# Push-It-V1_1.net
KiCad netlist of a schematic drawn in EAGLE
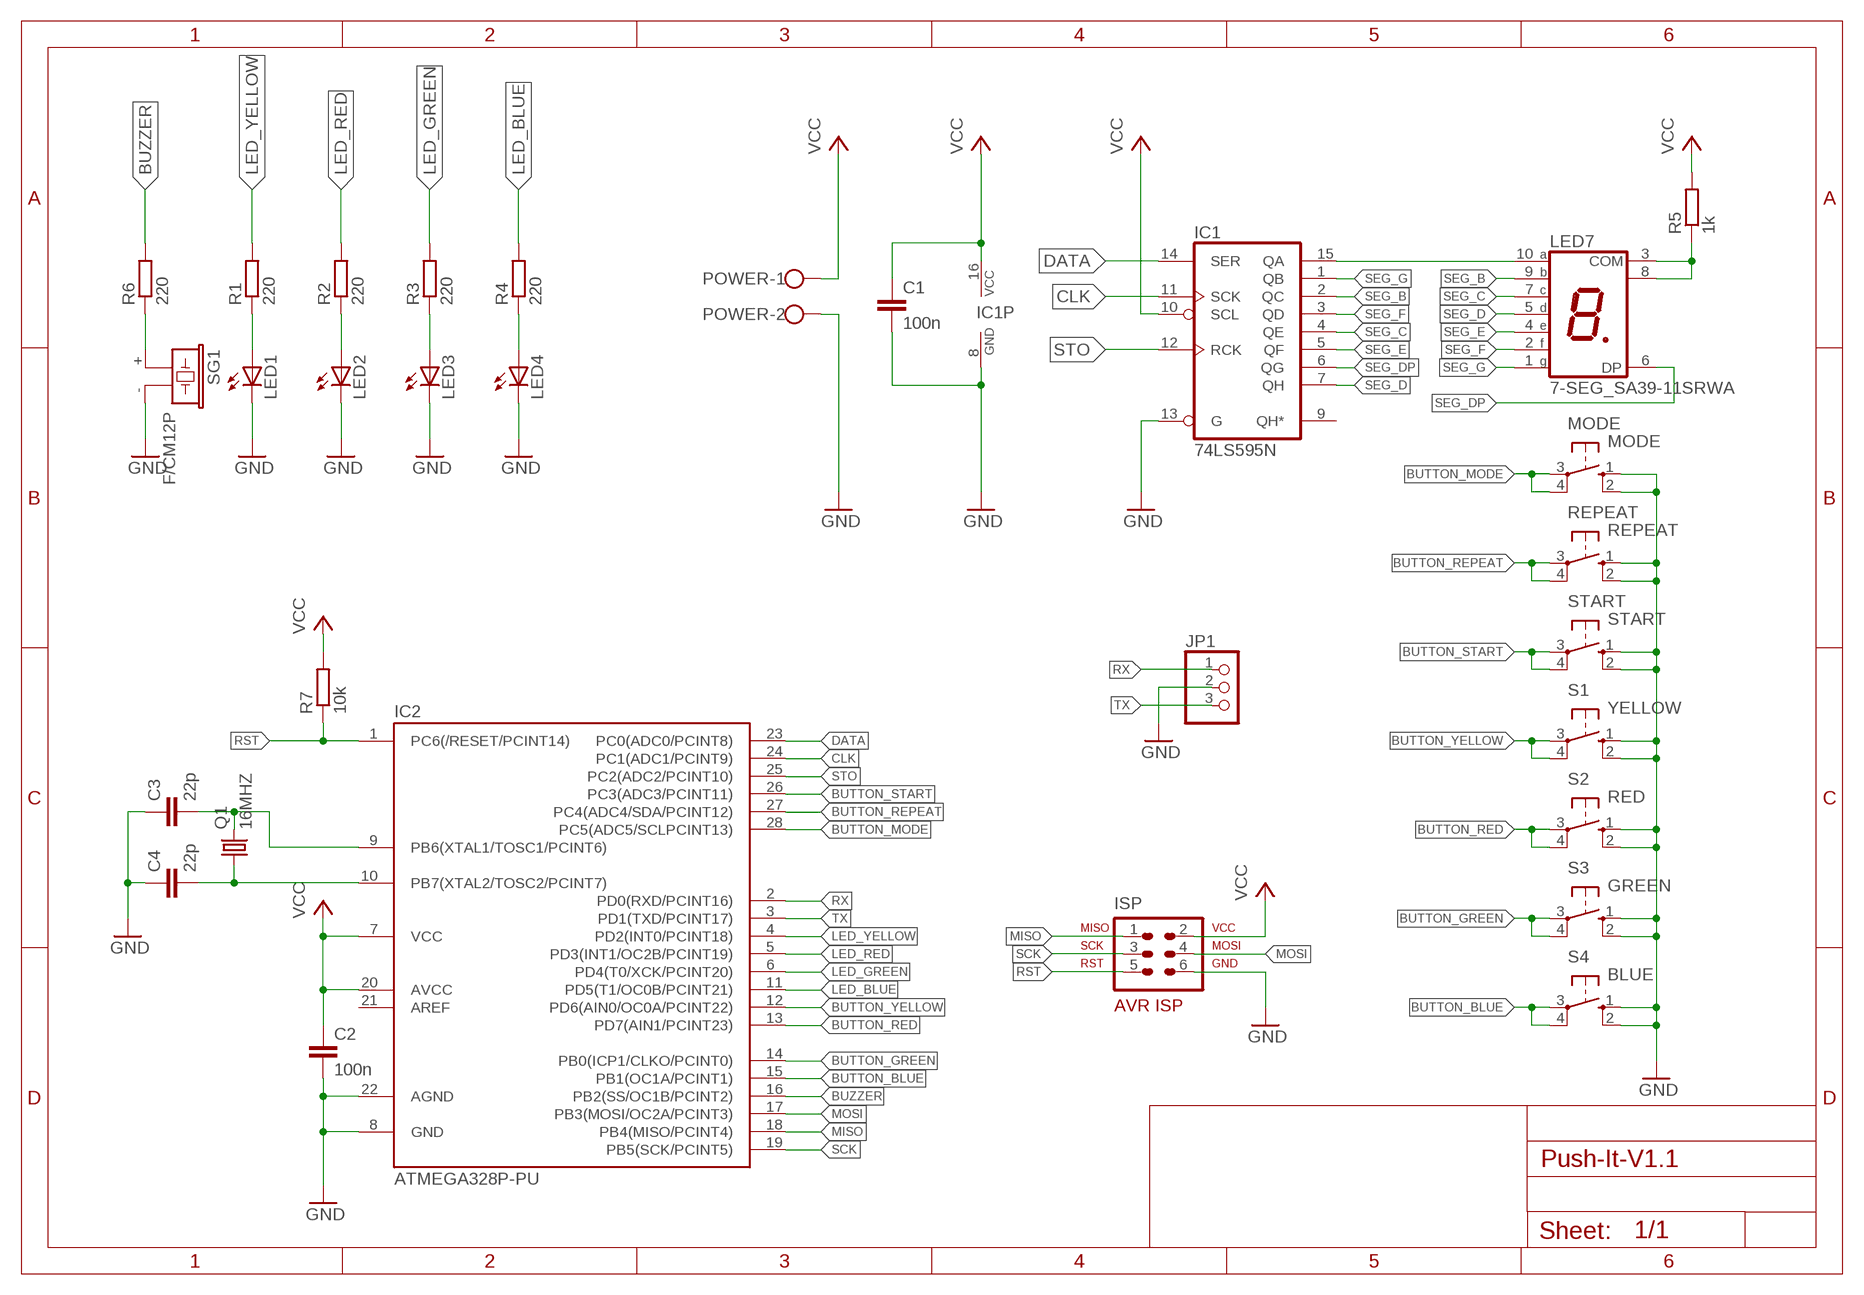
[diagram p0: schematic, sheet 1]

(export (version "E")
  (design (tool "Eeschema 10.0.6"))
  (components
    (comp (ref "C1")
      (value "100n")
      (footprint "eagle-import:C025-025X050")
      (libsource (lib "eagle-import") (part "C-EU025-025X050"))
    )
    (comp (ref "C2")
      (value "100n")
      (footprint "eagle-import:C025-025X050")
      (libsource (lib "eagle-import") (part "C-EU025-025X050"))
    )
    (comp (ref "C3")
      (value "22p")
      (footprint "eagle-import:C025-025X050")
      (libsource (lib "eagle-import") (part "C-EU025-025X050"))
    )
    (comp (ref "C4")
      (value "22p")
      (footprint "eagle-import:C025-025X050")
      (libsource (lib "eagle-import") (part "C-EU025-025X050"))
    )
    (comp (ref "IC1")
      (value "74LS595N")
      (footprint "eagle-import:DIL16")
      (libsource (lib "eagle-import") (part "74595NLS"))
    )
    (comp (ref "IC2")
      (value "ATMEGA328P-PU")
      (footprint "eagle-import:DIL28-3")
      (libsource (lib "eagle-import") (part "MEGA48/88/168-PU"))
    )
    (comp (ref "ISP")
      (value "AVR-ISP-6VERT")
      (footprint "eagle-import:AVR-ISP-6")
      (libsource (lib "eagle-import") (part "AVR-ISP-6VERT"))
    )
    (comp (ref "JP1")
      (value "PINHD-1X3/90")
      (footprint "eagle-import:1X03_90")
      (libsource (lib "eagle-import") (part "PINHD-1X3/90"))
    )
    (comp (ref "LED1")
      (value "LED10MM")
      (footprint "eagle-import:LED10MM")
      (libsource (lib "eagle-import") (part "LED10MM"))
    )
    (comp (ref "LED2")
      (value "LED10MM")
      (footprint "eagle-import:LED10MM")
      (libsource (lib "eagle-import") (part "LED10MM"))
    )
    (comp (ref "LED3")
      (value "LED10MM")
      (footprint "eagle-import:LED10MM")
      (libsource (lib "eagle-import") (part "LED10MM"))
    )
    (comp (ref "LED4")
      (value "LED10MM")
      (footprint "eagle-import:LED10MM")
      (libsource (lib "eagle-import") (part "LED10MM"))
    )
    (comp (ref "LED7")
      (value "7-SEG_SA39-11SRWA")
      (footprint "eagle-import:SA39-11SRWA")
      (libsource (lib "eagle-import") (part "7-SEG_SA39-11SRWA"))
    )
    (comp (ref "MODE")
      (value "MODE")
      (footprint "eagle-import:B3F-10XX")
      (fields (field (name "MPN") "B3F-1000"))
      (libsource (lib "eagle-import") (part "10-XX"))
    )
    (comp (ref "POWER")
      (value "W237-102")
      (footprint "eagle-import:W237-102")
      (fields (field (name "MPN") "237-102"))
      (libsource (lib "eagle-import") (part "W237-102"))
    )
    (comp (ref "Q1")
      (value "16MHZ")
      (footprint "eagle-import:HC49_S")
      (libsource (lib "eagle-import") (part "CRYSTALHC49S"))
    )
    (comp (ref "R1")
      (value "220")
      (footprint "eagle-import:0207_7")
      (libsource (lib "eagle-import") (part "R-EU_0207/7"))
    )
    (comp (ref "R2")
      (value "220")
      (footprint "eagle-import:0207_7")
      (libsource (lib "eagle-import") (part "R-EU_0207/7"))
    )
    (comp (ref "R3")
      (value "220")
      (footprint "eagle-import:0207_7")
      (libsource (lib "eagle-import") (part "R-EU_0207/7"))
    )
    (comp (ref "R4")
      (value "220")
      (footprint "eagle-import:0207_7")
      (libsource (lib "eagle-import") (part "R-EU_0207/7"))
    )
    (comp (ref "R5")
      (value "1k")
      (footprint "eagle-import:0207_7")
      (libsource (lib "eagle-import") (part "R-EU_0207/7"))
    )
    (comp (ref "R6")
      (value "220")
      (footprint "eagle-import:0207_7")
      (libsource (lib "eagle-import") (part "R-EU_0207/7"))
    )
    (comp (ref "R7")
      (value "10k")
      (footprint "eagle-import:0207_7")
      (libsource (lib "eagle-import") (part "R-EU_0207/7"))
    )
    (comp (ref "REPEAT")
      (value "REPEAT")
      (footprint "eagle-import:B3F-10XX")
      (fields (field (name "MPN") "B3F-1000"))
      (libsource (lib "eagle-import") (part "10-XX"))
    )
    (comp (ref "S1")
      (value "YELLOW")
      (footprint "eagle-import:B3F-10XX")
      (fields (field (name "MPN") "B3F-1000"))
      (libsource (lib "eagle-import") (part "10-XX"))
    )
    (comp (ref "S2")
      (value "RED")
      (footprint "eagle-import:B3F-10XX")
      (fields (field (name "MPN") "B3F-1000"))
      (libsource (lib "eagle-import") (part "10-XX"))
    )
    (comp (ref "S3")
      (value "GREEN")
      (footprint "eagle-import:B3F-10XX")
      (fields (field (name "MPN") "B3F-1000"))
      (libsource (lib "eagle-import") (part "10-XX"))
    )
    (comp (ref "S4")
      (value "BLUE")
      (footprint "eagle-import:B3F-10XX")
      (fields (field (name "MPN") "B3F-1000"))
      (libsource (lib "eagle-import") (part "10-XX"))
    )
    (comp (ref "SG1")
      (value "F/CM12P")
      (footprint "eagle-import:F_CM12P")
      (libsource (lib "eagle-import") (part "F/CM12P"))
    )
    (comp (ref "START")
      (value "START")
      (footprint "eagle-import:B3F-10XX")
      (fields (field (name "MPN") "B3F-1000"))
      (libsource (lib "eagle-import") (part "10-XX"))
    )
  )
  (nets
    (net (code "1") (name "BUTTON_BLUE") (class "Default")
      (node (ref "IC2") (pin "15") (pinfunction "PB1(OC1A/PCINT1)_15") (pintype "bidirectional"))
      (node (ref "S4") (pin "3") (pinfunction "P_3") (pintype "passive"))
      (node (ref "S4") (pin "4") (pinfunction "P1_4") (pintype "passive"))
    )
    (net (code "2") (name "BUTTON_GREEN") (class "Default")
      (node (ref "IC2") (pin "14") (pinfunction "PB0(ICP1/CLKO/PCINT0)_14") (pintype "bidirectional"))
      (node (ref "S3") (pin "3") (pinfunction "P_3") (pintype "passive"))
      (node (ref "S3") (pin "4") (pinfunction "P1_4") (pintype "passive"))
    )
    (net (code "3") (name "BUTTON_MODE") (class "Default")
      (node (ref "IC2") (pin "28") (pinfunction "PC5(ADC5/SCLPCINT13)_28") (pintype "bidirectional"))
      (node (ref "MODE") (pin "3") (pinfunction "P_3") (pintype "passive"))
      (node (ref "MODE") (pin "4") (pinfunction "P1_4") (pintype "passive"))
    )
    (net (code "4") (name "BUTTON_RED") (class "Default")
      (node (ref "IC2") (pin "13") (pinfunction "PD7(AIN1/PCINT23)_13") (pintype "bidirectional"))
      (node (ref "S2") (pin "3") (pinfunction "P_3") (pintype "passive"))
      (node (ref "S2") (pin "4") (pinfunction "P1_4") (pintype "passive"))
    )
    (net (code "5") (name "BUTTON_REPEAT") (class "Default")
      (node (ref "IC2") (pin "27") (pinfunction "PC4(ADC4/SDA/PCINT12)_27") (pintype "bidirectional"))
      (node (ref "REPEAT") (pin "3") (pinfunction "P_3") (pintype "passive"))
      (node (ref "REPEAT") (pin "4") (pinfunction "P1_4") (pintype "passive"))
    )
    (net (code "6") (name "BUTTON_START") (class "Default")
      (node (ref "IC2") (pin "26") (pinfunction "PC3(ADC3/PCINT11)_26") (pintype "bidirectional"))
      (node (ref "START") (pin "3") (pinfunction "P_3") (pintype "passive"))
      (node (ref "START") (pin "4") (pinfunction "P1_4") (pintype "passive"))
    )
    (net (code "7") (name "BUTTON_YELLOW") (class "Default")
      (node (ref "IC2") (pin "12") (pinfunction "PD6(AIN0/OC0A/PCINT22)_12") (pintype "bidirectional"))
      (node (ref "S1") (pin "3") (pinfunction "P_3") (pintype "passive"))
      (node (ref "S1") (pin "4") (pinfunction "P1_4") (pintype "passive"))
    )
    (net (code "8") (name "BUZZER") (class "Default")
      (node (ref "IC2") (pin "16") (pinfunction "PB2(SS/OC1B/PCINT2)_16") (pintype "bidirectional"))
      (node (ref "R6") (pin "2") (pinfunction "2_2") (pintype "passive"))
    )
    (net (code "9") (name "CLK") (class "Default")
      (node (ref "IC1") (pin "11") (pinfunction "SCK_11") (pintype "input"))
      (node (ref "IC2") (pin "24") (pinfunction "PC1(ADC1/PCINT9)_24") (pintype "bidirectional"))
    )
    (net (code "10") (name "DATA") (class "Default")
      (node (ref "IC1") (pin "14") (pinfunction "SER_14") (pintype "input"))
      (node (ref "IC2") (pin "23") (pinfunction "PC0(ADC0/PCINT8)_23") (pintype "bidirectional"))
    )
    (net (code "11") (name "GND") (class "Default")
      (node (ref "C1") (pin "2") (pinfunction "2_2") (pintype "passive"))
      (node (ref "C2") (pin "2") (pinfunction "2_2") (pintype "passive"))
      (node (ref "C3") (pin "1") (pinfunction "1_1") (pintype "passive"))
      (node (ref "C4") (pin "1") (pinfunction "1_1") (pintype "passive"))
      (node (ref "IC1") (pin "13") (pinfunction "G_13") (pintype "input"))
      (node (ref "IC1") (pin "8") (pinfunction "GND_8") (pintype "power_in"))
      (node (ref "IC2") (pin "22") (pinfunction "AGND_22") (pintype "power_in"))
      (node (ref "IC2") (pin "8") (pinfunction "GND_8") (pintype "power_in"))
      (node (ref "ISP") (pin "6") (pinfunction "6_6") (pintype "passive"))
      (node (ref "JP1") (pin "2") (pinfunction "2_2") (pintype "passive"))
      (node (ref "LED1") (pin "K") (pinfunction "C_K") (pintype "passive"))
      (node (ref "LED2") (pin "K") (pinfunction "C_K") (pintype "passive"))
      (node (ref "LED3") (pin "K") (pinfunction "C_K") (pintype "passive"))
      (node (ref "LED4") (pin "K") (pinfunction "C_K") (pintype "passive"))
      (node (ref "MODE") (pin "1") (pinfunction "S_1") (pintype "passive"))
      (node (ref "MODE") (pin "2") (pinfunction "S1_2") (pintype "passive"))
      (node (ref "POWER") (pin "2") (pinfunction "KL_2") (pintype "passive"))
      (node (ref "REPEAT") (pin "1") (pinfunction "S_1") (pintype "passive"))
      (node (ref "REPEAT") (pin "2") (pinfunction "S1_2") (pintype "passive"))
      (node (ref "S1") (pin "1") (pinfunction "S_1") (pintype "passive"))
      (node (ref "S1") (pin "2") (pinfunction "S1_2") (pintype "passive"))
      (node (ref "S2") (pin "1") (pinfunction "S_1") (pintype "passive"))
      (node (ref "S2") (pin "2") (pinfunction "S1_2") (pintype "passive"))
      (node (ref "S3") (pin "1") (pinfunction "S_1") (pintype "passive"))
      (node (ref "S3") (pin "2") (pinfunction "S1_2") (pintype "passive"))
      (node (ref "S4") (pin "1") (pinfunction "S_1") (pintype "passive"))
      (node (ref "S4") (pin "2") (pinfunction "S1_2") (pintype "passive"))
      (node (ref "SG1") (pin "-") (pinfunction "2_-") (pintype "passive"))
      (node (ref "START") (pin "1") (pinfunction "S_1") (pintype "passive"))
      (node (ref "START") (pin "2") (pinfunction "S1_2") (pintype "passive"))
    )
    (net (code "12") (name "LED_BLUE") (class "Default")
      (node (ref "IC2") (pin "11") (pinfunction "PD5(T1/OC0B/PCINT21)_11") (pintype "bidirectional"))
      (node (ref "R4") (pin "2") (pinfunction "2_2") (pintype "passive"))
    )
    (net (code "13") (name "LED_GREEN") (class "Default")
      (node (ref "IC2") (pin "6") (pinfunction "PD4(T0/XCK/PCINT20)_6") (pintype "bidirectional"))
      (node (ref "R3") (pin "2") (pinfunction "2_2") (pintype "passive"))
    )
    (net (code "14") (name "LED_RED") (class "Default")
      (node (ref "IC2") (pin "5") (pinfunction "PD3(INT1/OC2B/PCINT19)_5") (pintype "bidirectional"))
      (node (ref "R2") (pin "2") (pinfunction "2_2") (pintype "passive"))
    )
    (net (code "15") (name "LED_YELLOW") (class "Default")
      (node (ref "IC2") (pin "4") (pinfunction "PD2(INT0/PCINT18)_4") (pintype "bidirectional"))
      (node (ref "R1") (pin "2") (pinfunction "2_2") (pintype "passive"))
    )
    (net (code "16") (name "MISO") (class "Default")
      (node (ref "IC2") (pin "18") (pinfunction "PB4(MISO/PCINT4)_18") (pintype "bidirectional"))
      (node (ref "ISP") (pin "1") (pinfunction "1_1") (pintype "passive"))
    )
    (net (code "17") (name "MOSI") (class "Default")
      (node (ref "IC2") (pin "17") (pinfunction "PB3(MOSI/OC2A/PCINT3)_17") (pintype "bidirectional"))
      (node (ref "ISP") (pin "4") (pinfunction "4_4") (pintype "passive"))
    )
    (net (code "18") (name "Net-(IC1A-QA)") (class "Default")
      (node (ref "IC1") (pin "15") (pinfunction "QA_15") (pintype "tri_state"))
      (node (ref "LED7") (pin "10") (pinfunction "A_10") (pintype "passive"))
    )
    (net (code "19") (name "Net-(IC2-PB6(XTAL1{slash}TOSC1{slash}PCINT6))") (class "Default")
      (node (ref "C3") (pin "2") (pinfunction "2_2") (pintype "passive"))
      (node (ref "IC2") (pin "9") (pinfunction "PB6(XTAL1/TOSC1/PCINT6)_9") (pintype "bidirectional"))
      (node (ref "Q1") (pin "2") (pinfunction "2_2") (pintype "passive"))
    )
    (net (code "20") (name "Net-(IC2-PB7(XTAL2{slash}TOSC2{slash}PCINT7))") (class "Default")
      (node (ref "C4") (pin "2") (pinfunction "2_2") (pintype "passive"))
      (node (ref "IC2") (pin "10") (pinfunction "PB7(XTAL2/TOSC2/PCINT7)_10") (pintype "bidirectional"))
      (node (ref "Q1") (pin "1") (pinfunction "1_1") (pintype "passive"))
    )
    (net (code "21") (name "Net-(LED1-PadA)") (class "Default")
      (node (ref "LED1") (pin "A") (pinfunction "A_A") (pintype "passive"))
      (node (ref "R1") (pin "1") (pinfunction "1_1") (pintype "passive"))
    )
    (net (code "22") (name "Net-(LED2-PadA)") (class "Default")
      (node (ref "LED2") (pin "A") (pinfunction "A_A") (pintype "passive"))
      (node (ref "R2") (pin "1") (pinfunction "1_1") (pintype "passive"))
    )
    (net (code "23") (name "Net-(LED3-PadA)") (class "Default")
      (node (ref "LED3") (pin "A") (pinfunction "A_A") (pintype "passive"))
      (node (ref "R3") (pin "1") (pinfunction "1_1") (pintype "passive"))
    )
    (net (code "24") (name "Net-(LED4-PadA)") (class "Default")
      (node (ref "LED4") (pin "A") (pinfunction "A_A") (pintype "passive"))
      (node (ref "R4") (pin "1") (pinfunction "1_1") (pintype "passive"))
    )
    (net (code "25") (name "Net-(LED7-COM-Pad3)") (class "Default")
      (node (ref "LED7") (pin "3") (pinfunction "COM_3") (pintype "passive"))
      (node (ref "LED7") (pin "8") (pinfunction "COM_8") (pintype "passive"))
      (node (ref "R5") (pin "1") (pinfunction "1_1") (pintype "passive"))
    )
    (net (code "26") (name "Net-(SG1-1)") (class "Default")
      (node (ref "R6") (pin "1") (pinfunction "1_1") (pintype "passive"))
      (node (ref "SG1") (pin "+") (pinfunction "1_+") (pintype "passive"))
    )
    (net (code "27") (name "RST") (class "Default")
      (node (ref "IC2") (pin "1") (pinfunction "PC6(/RESET/PCINT14)_1") (pintype "bidirectional"))
      (node (ref "ISP") (pin "5") (pinfunction "5_5") (pintype "passive"))
      (node (ref "R7") (pin "1") (pinfunction "1_1") (pintype "passive"))
    )
    (net (code "28") (name "RX") (class "Default")
      (node (ref "IC2") (pin "2") (pinfunction "PD0(RXD/PCINT16)_2") (pintype "bidirectional"))
      (node (ref "JP1") (pin "1") (pinfunction "1_1") (pintype "passive"))
    )
    (net (code "29") (name "SCK") (class "Default")
      (node (ref "IC2") (pin "19") (pinfunction "PB5(SCK/PCINT5)_19") (pintype "bidirectional"))
      (node (ref "ISP") (pin "3") (pinfunction "3_3") (pintype "passive"))
    )
    (net (code "30") (name "SEG_B") (class "Default")
      (node (ref "IC1") (pin "2") (pinfunction "QC_2") (pintype "tri_state"))
      (node (ref "LED7") (pin "9") (pinfunction "B_9") (pintype "passive"))
    )
    (net (code "31") (name "SEG_C") (class "Default")
      (node (ref "IC1") (pin "4") (pinfunction "QE_4") (pintype "tri_state"))
      (node (ref "LED7") (pin "7") (pinfunction "C_7") (pintype "passive"))
    )
    (net (code "32") (name "SEG_D") (class "Default")
      (node (ref "IC1") (pin "7") (pinfunction "QH_7") (pintype "tri_state"))
      (node (ref "LED7") (pin "5") (pinfunction "D_5") (pintype "passive"))
    )
    (net (code "33") (name "SEG_DP") (class "Default")
      (node (ref "IC1") (pin "6") (pinfunction "QG_6") (pintype "tri_state"))
      (node (ref "LED7") (pin "6") (pinfunction "DP_6") (pintype "passive"))
    )
    (net (code "34") (name "SEG_E") (class "Default")
      (node (ref "IC1") (pin "5") (pinfunction "QF_5") (pintype "tri_state"))
      (node (ref "LED7") (pin "4") (pinfunction "E_4") (pintype "passive"))
    )
    (net (code "35") (name "SEG_F") (class "Default")
      (node (ref "IC1") (pin "3") (pinfunction "QD_3") (pintype "tri_state"))
      (node (ref "LED7") (pin "2") (pinfunction "F_2") (pintype "passive"))
    )
    (net (code "36") (name "SEG_G") (class "Default")
      (node (ref "IC1") (pin "1") (pinfunction "QB_1") (pintype "tri_state"))
      (node (ref "LED7") (pin "1") (pinfunction "G_1") (pintype "passive"))
    )
    (net (code "37") (name "STO") (class "Default")
      (node (ref "IC1") (pin "12") (pinfunction "RCK_12") (pintype "input"))
      (node (ref "IC2") (pin "25") (pinfunction "PC2(ADC2/PCINT10)_25") (pintype "bidirectional"))
    )
    (net (code "38") (name "TX") (class "Default")
      (node (ref "IC2") (pin "3") (pinfunction "PD1(TXD/PCINT17)_3") (pintype "bidirectional"))
      (node (ref "JP1") (pin "3") (pinfunction "3_3") (pintype "passive"))
    )
    (net (code "39") (name "VCC") (class "Default")
      (node (ref "C1") (pin "1") (pinfunction "1_1") (pintype "passive"))
      (node (ref "C2") (pin "1") (pinfunction "1_1") (pintype "passive"))
      (node (ref "IC1") (pin "10") (pinfunction "SCL_10") (pintype "input"))
      (node (ref "IC1") (pin "16") (pinfunction "VCC_16") (pintype "power_in"))
      (node (ref "IC2") (pin "20") (pinfunction "AVCC_20") (pintype "passive"))
      (node (ref "IC2") (pin "7") (pinfunction "VCC_7") (pintype "power_in"))
      (node (ref "ISP") (pin "2") (pinfunction "2_2") (pintype "passive"))
      (node (ref "POWER") (pin "1") (pinfunction "KL_1") (pintype "passive"))
      (node (ref "R5") (pin "2") (pinfunction "2_2") (pintype "passive"))
      (node (ref "R7") (pin "2") (pinfunction "2_2") (pintype "passive"))
    )
    (net (code "40") (name "unconnected-(IC1A-QH*-Pad9)") (class "Default")
      (node (ref "IC1") (pin "9") (pinfunction "QH*_9") (pintype "tri_state"))
    )
    (net (code "41") (name "unconnected-(IC2-AREF-Pad21)") (class "Default")
      (node (ref "IC2") (pin "21") (pinfunction "AREF_21") (pintype "passive"))
    )
  )
)
